# LDR_array.net
KiCad netlist of a schematic drawn in EAGLE
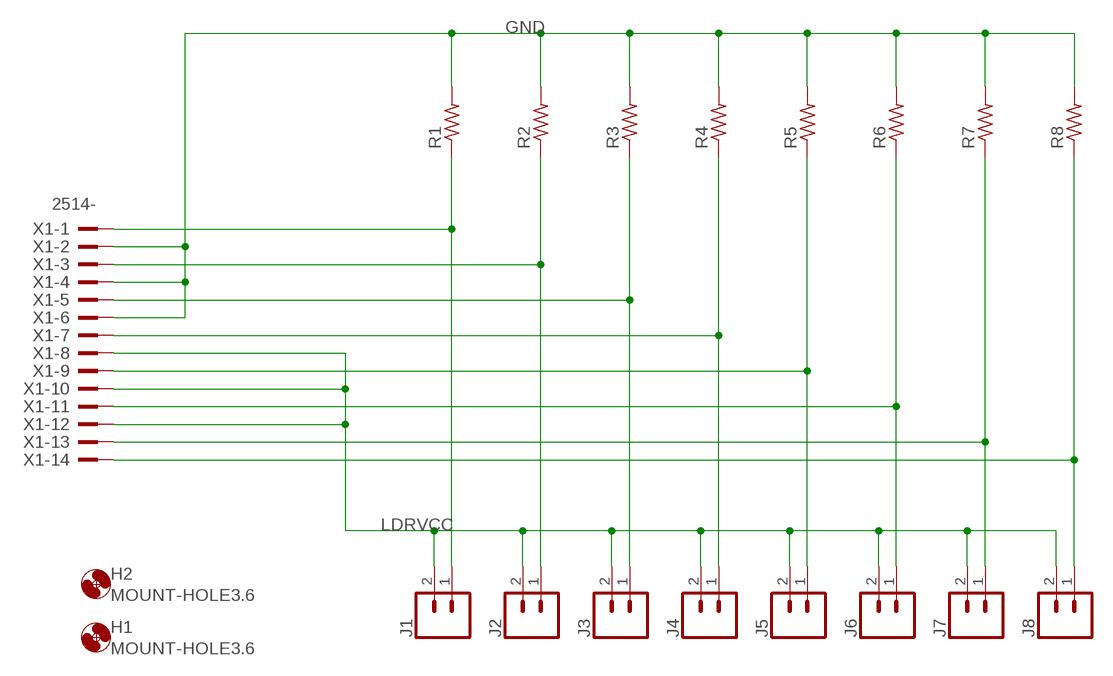
[diagram p0: schematic, sheet 1]

(export (version "E")
  (design (tool "Eeschema 10.0.6"))
  (components
    (comp (ref "H1")
      (value "MOUNT-HOLE3.6")
      (footprint "eagle-import:3,6")
      (libsource (lib "eagle-import") (part "MOUNT-HOLE3.6"))
    )
    (comp (ref "H2")
      (value "MOUNT-HOLE3.6")
      (footprint "eagle-import:3,6")
      (libsource (lib "eagle-import") (part "MOUNT-HOLE3.6"))
    )
    (comp (ref "J1")
      (value "CONN_023.5MM_LOCK")
      (footprint "eagle-import:SCREWTERMINAL-3.5MM-2_LOCK")
      (libsource (lib "eagle-import") (part "CONN_023.5MM_LOCK"))
    )
    (comp (ref "J2")
      (value "CONN_023.5MM_LOCK")
      (footprint "eagle-import:SCREWTERMINAL-3.5MM-2_LOCK")
      (libsource (lib "eagle-import") (part "CONN_023.5MM_LOCK"))
    )
    (comp (ref "J3")
      (value "CONN_023.5MM_LOCK")
      (footprint "eagle-import:SCREWTERMINAL-3.5MM-2_LOCK")
      (libsource (lib "eagle-import") (part "CONN_023.5MM_LOCK"))
    )
    (comp (ref "J4")
      (value "CONN_023.5MM_LOCK")
      (footprint "eagle-import:SCREWTERMINAL-3.5MM-2_LOCK")
      (libsource (lib "eagle-import") (part "CONN_023.5MM_LOCK"))
    )
    (comp (ref "J5")
      (value "CONN_023.5MM_LOCK")
      (footprint "eagle-import:SCREWTERMINAL-3.5MM-2_LOCK")
      (libsource (lib "eagle-import") (part "CONN_023.5MM_LOCK"))
    )
    (comp (ref "J6")
      (value "CONN_023.5MM_LOCK")
      (footprint "eagle-import:SCREWTERMINAL-3.5MM-2_LOCK")
      (libsource (lib "eagle-import") (part "CONN_023.5MM_LOCK"))
    )
    (comp (ref "J7")
      (value "CONN_023.5MM_LOCK")
      (footprint "eagle-import:SCREWTERMINAL-3.5MM-2_LOCK")
      (libsource (lib "eagle-import") (part "CONN_023.5MM_LOCK"))
    )
    (comp (ref "J8")
      (value "CONN_023.5MM_LOCK")
      (footprint "eagle-import:SCREWTERMINAL-3.5MM-2_LOCK")
      (libsource (lib "eagle-import") (part "CONN_023.5MM_LOCK"))
    )
    (comp (ref "R1")
      (value "R-US_0204/7")
      (footprint "eagle-import:0204_7")
      (libsource (lib "eagle-import") (part "R-US_0204/7"))
    )
    (comp (ref "R2")
      (value "R-US_0204/7")
      (footprint "eagle-import:0204_7")
      (libsource (lib "eagle-import") (part "R-US_0204/7"))
    )
    (comp (ref "R3")
      (value "R-US_0204/7")
      (footprint "eagle-import:0204_7")
      (libsource (lib "eagle-import") (part "R-US_0204/7"))
    )
    (comp (ref "R4")
      (value "R-US_0204/7")
      (footprint "eagle-import:0204_7")
      (libsource (lib "eagle-import") (part "R-US_0204/7"))
    )
    (comp (ref "R5")
      (value "R-US_0204/7")
      (footprint "eagle-import:0204_7")
      (libsource (lib "eagle-import") (part "R-US_0204/7"))
    )
    (comp (ref "R6")
      (value "R-US_0204/7")
      (footprint "eagle-import:0204_7")
      (libsource (lib "eagle-import") (part "R-US_0204/7"))
    )
    (comp (ref "R7")
      (value "R-US_0204/7")
      (footprint "eagle-import:0204_7")
      (libsource (lib "eagle-import") (part "R-US_0204/7"))
    )
    (comp (ref "R8")
      (value "R-US_0204/7")
      (footprint "eagle-import:0204_7")
      (libsource (lib "eagle-import") (part "R-US_0204/7"))
    )
    (comp (ref "X1")
      (value "2514-")
      (footprint "eagle-import:PAK100_2500-14")
      (libsource (lib "eagle-import") (part "2514-"))
    )
  )
  (nets
    (net (code "1") (name "/GND") (class "Default")
      (node (ref "R1") (pin "2") (pinfunction "2_2") (pintype "passive"))
      (node (ref "R2") (pin "2") (pinfunction "2_2") (pintype "passive"))
      (node (ref "R3") (pin "2") (pinfunction "2_2") (pintype "passive"))
      (node (ref "R4") (pin "2") (pinfunction "2_2") (pintype "passive"))
      (node (ref "R5") (pin "2") (pinfunction "2_2") (pintype "passive"))
      (node (ref "R6") (pin "2") (pinfunction "2_2") (pintype "passive"))
      (node (ref "R7") (pin "2") (pinfunction "2_2") (pintype "passive"))
      (node (ref "R8") (pin "2") (pinfunction "2_2") (pintype "passive"))
      (node (ref "X1") (pin "2") (pinfunction "KL_2") (pintype "passive"))
      (node (ref "X1") (pin "4") (pinfunction "KL_4") (pintype "passive"))
      (node (ref "X1") (pin "6") (pinfunction "KL_6") (pintype "passive"))
    )
    (net (code "2") (name "/LDRVCC") (class "Default")
      (node (ref "J1") (pin "2") (pinfunction "2_2") (pintype "passive"))
      (node (ref "J2") (pin "2") (pinfunction "2_2") (pintype "passive"))
      (node (ref "J3") (pin "2") (pinfunction "2_2") (pintype "passive"))
      (node (ref "J4") (pin "2") (pinfunction "2_2") (pintype "passive"))
      (node (ref "J5") (pin "2") (pinfunction "2_2") (pintype "passive"))
      (node (ref "J6") (pin "2") (pinfunction "2_2") (pintype "passive"))
      (node (ref "J7") (pin "2") (pinfunction "2_2") (pintype "passive"))
      (node (ref "J8") (pin "2") (pinfunction "2_2") (pintype "passive"))
      (node (ref "X1") (pin "10") (pinfunction "KL_10") (pintype "passive"))
      (node (ref "X1") (pin "12") (pinfunction "KL_12") (pintype "passive"))
      (node (ref "X1") (pin "8") (pinfunction "KL_8") (pintype "passive"))
    )
    (net (code "3") (name "Net-(X1A-KL)") (class "Default")
      (node (ref "J1") (pin "1") (pinfunction "1_1") (pintype "passive"))
      (node (ref "R1") (pin "1") (pinfunction "1_1") (pintype "passive"))
      (node (ref "X1") (pin "1") (pinfunction "KL_1") (pintype "passive"))
    )
    (net (code "4") (name "Net-(X1C-KL)") (class "Default")
      (node (ref "J6") (pin "1") (pinfunction "1_1") (pintype "passive"))
      (node (ref "R6") (pin "1") (pinfunction "1_1") (pintype "passive"))
      (node (ref "X1") (pin "11") (pinfunction "KL_11") (pintype "passive"))
    )
    (net (code "5") (name "Net-(X1E-KL)") (class "Default")
      (node (ref "J7") (pin "1") (pinfunction "1_1") (pintype "passive"))
      (node (ref "R7") (pin "1") (pinfunction "1_1") (pintype "passive"))
      (node (ref "X1") (pin "13") (pinfunction "KL_13") (pintype "passive"))
    )
    (net (code "6") (name "Net-(X1F-KL)") (class "Default")
      (node (ref "J8") (pin "1") (pinfunction "1_1") (pintype "passive"))
      (node (ref "R8") (pin "1") (pinfunction "1_1") (pintype "passive"))
      (node (ref "X1") (pin "14") (pinfunction "KL_14") (pintype "passive"))
    )
    (net (code "7") (name "Net-(X1H-KL)") (class "Default")
      (node (ref "J2") (pin "1") (pinfunction "1_1") (pintype "passive"))
      (node (ref "R2") (pin "1") (pinfunction "1_1") (pintype "passive"))
      (node (ref "X1") (pin "3") (pinfunction "KL_3") (pintype "passive"))
    )
    (net (code "8") (name "Net-(X1J-KL)") (class "Default")
      (node (ref "J3") (pin "1") (pinfunction "1_1") (pintype "passive"))
      (node (ref "R3") (pin "1") (pinfunction "1_1") (pintype "passive"))
      (node (ref "X1") (pin "5") (pinfunction "KL_5") (pintype "passive"))
    )
    (net (code "9") (name "Net-(X1L-KL)") (class "Default")
      (node (ref "J4") (pin "1") (pinfunction "1_1") (pintype "passive"))
      (node (ref "R4") (pin "1") (pinfunction "1_1") (pintype "passive"))
      (node (ref "X1") (pin "7") (pinfunction "KL_7") (pintype "passive"))
    )
    (net (code "10") (name "Net-(X1N-KL)") (class "Default")
      (node (ref "J5") (pin "1") (pinfunction "1_1") (pintype "passive"))
      (node (ref "R5") (pin "1") (pinfunction "1_1") (pintype "passive"))
      (node (ref "X1") (pin "9") (pinfunction "KL_9") (pintype "passive"))
    )
  )
)
